# board.net
KiCad netlist of a schematic drawn in EAGLE
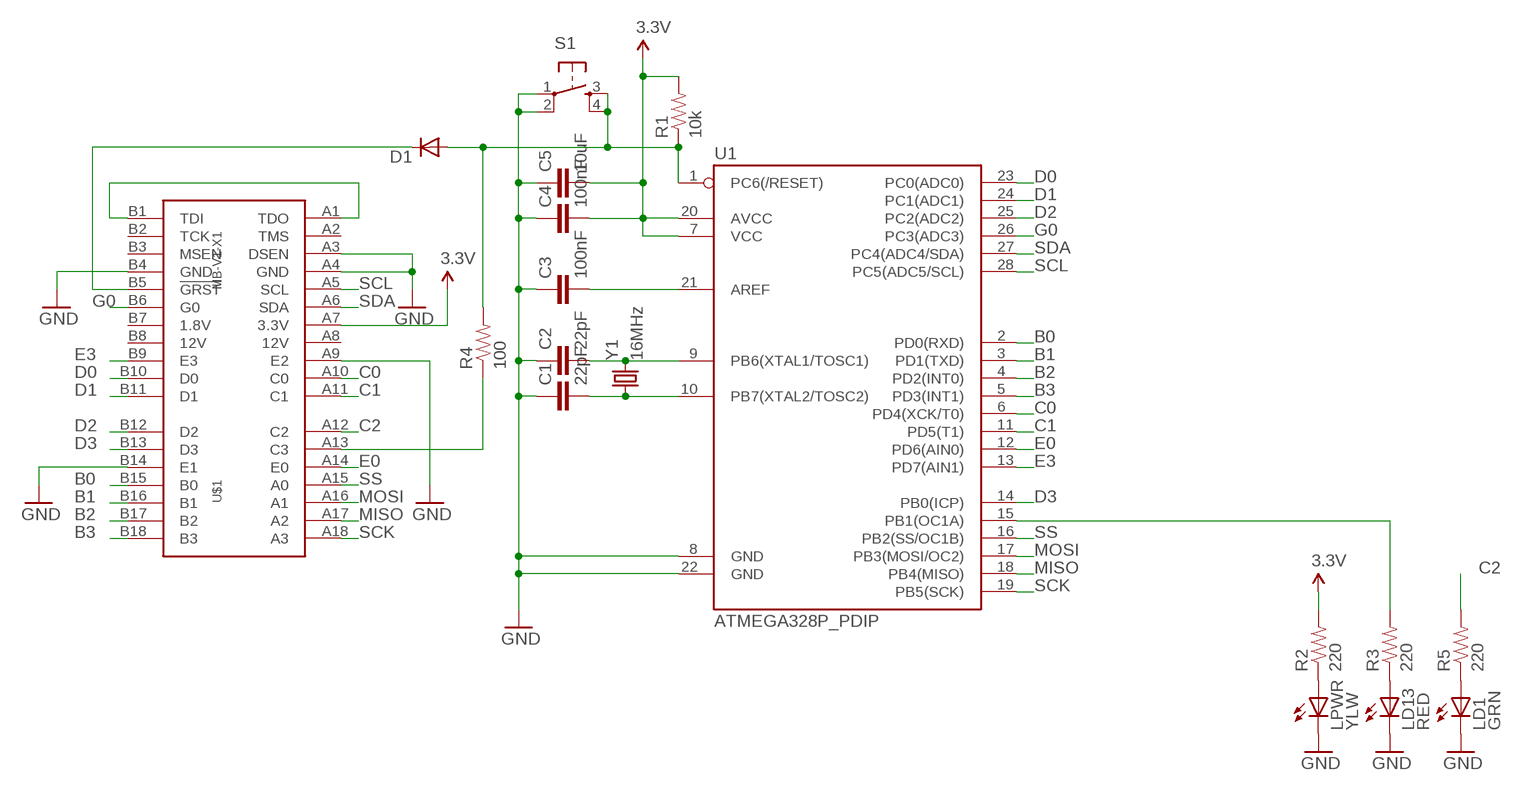
[diagram p0: schematic, sheet 1]

(export (version "E")
  (design (tool "Eeschema 10.0.6"))
  (components
    (comp (ref "C1")
      (value "22pF")
      (footprint "eagle-import:0402-CAP")
      (libsource (lib "eagle-import") (part "CAP0402-CAP"))
    )
    (comp (ref "C2")
      (value "22pF")
      (footprint "eagle-import:0402-CAP")
      (libsource (lib "eagle-import") (part "CAP0402-CAP"))
    )
    (comp (ref "C3")
      (value "100nF")
      (footprint "eagle-import:0402-CAP")
      (libsource (lib "eagle-import") (part "CAP0402-CAP"))
    )
    (comp (ref "C4")
      (value "100nF")
      (footprint "eagle-import:0402-CAP")
      (libsource (lib "eagle-import") (part "CAP0402-CAP"))
    )
    (comp (ref "C5")
      (value "10uF")
      (footprint "eagle-import:0805")
      (libsource (lib "eagle-import") (part "CAP0805"))
    )
    (comp (ref "D1")
      (value "DIODE1N4148")
      (footprint "eagle-import:DIODE-1N4148")
      (libsource (lib "eagle-import") (part "DIODE1N4148"))
    )
    (comp (ref "LD1")
      (value "GRN")
      (footprint "eagle-import:LED-0603")
      (libsource (lib "eagle-import") (part "LED-RED0603"))
    )
    (comp (ref "LD13")
      (value "RED")
      (footprint "eagle-import:LED-0603")
      (libsource (lib "eagle-import") (part "LED-RED0603"))
    )
    (comp (ref "LPWR")
      (value "YLW")
      (footprint "eagle-import:LED-0603")
      (libsource (lib "eagle-import") (part "LED-RED0603"))
    )
    (comp (ref "R1")
      (value "10k")
      (footprint "eagle-import:0603-RES")
      (libsource (lib "eagle-import") (part "kmod-passives_RESISTOR0603"))
    )
    (comp (ref "R2")
      (value "220")
      (footprint "eagle-import:0603-RES")
      (libsource (lib "eagle-import") (part "RESISTOR0603"))
    )
    (comp (ref "R3")
      (value "220")
      (footprint "eagle-import:0603-RES")
      (libsource (lib "eagle-import") (part "RESISTOR0603"))
    )
    (comp (ref "R4")
      (value "100")
      (footprint "eagle-import:0603-RES")
      (libsource (lib "eagle-import") (part "kmod-passives_RESISTOR0603"))
    )
    (comp (ref "R5")
      (value "220")
      (footprint "eagle-import:0603-RES")
      (libsource (lib "eagle-import") (part "RESISTOR0603"))
    )
    (comp (ref "S1")
      (value "TAC_SWITCHPTH")
      (footprint "eagle-import:TACTILE-PTH")
      (libsource (lib "eagle-import") (part "TAC_SWITCHPTH"))
    )
    (comp (ref "U$1")
      (value "MB-V1-X1")
      (footprint "eagle-import:PCIE-X1-EDGE")
      (libsource (lib "eagle-import") (part "MB-V1-X1"))
    )
    (comp (ref "U1")
      (value "ATMEGA328P_PDIP")
      (footprint "eagle-import:DIL28-3")
      (libsource (lib "eagle-import") (part "ATMEGA328P_PDIP"))
    )
    (comp (ref "Y1")
      (value "16MHz")
      (footprint "eagle-import:HC49US")
      (libsource (lib "eagle-import") (part "CRYSTALHC49US"))
    )
  )
  (nets
    (net (code "1") (name "/B0") (class "Default")
      (node (ref "U$1") (pin "B15") (pinfunction "B0_B15") (pintype "bidirectional"))
      (node (ref "U1") (pin "2") (pinfunction "PD0(RXD)_2") (pintype "bidirectional"))
    )
    (net (code "2") (name "/B1") (class "Default")
      (node (ref "U$1") (pin "B16") (pinfunction "B1_B16") (pintype "bidirectional"))
      (node (ref "U1") (pin "3") (pinfunction "PD1(TXD)_3") (pintype "bidirectional"))
    )
    (net (code "3") (name "/B2") (class "Default")
      (node (ref "U$1") (pin "B17") (pinfunction "B2_B17") (pintype "bidirectional"))
      (node (ref "U1") (pin "4") (pinfunction "PD2(INT0)_4") (pintype "bidirectional"))
    )
    (net (code "4") (name "/B3") (class "Default")
      (node (ref "U$1") (pin "B18") (pinfunction "B3_B18") (pintype "bidirectional"))
      (node (ref "U1") (pin "5") (pinfunction "PD3(INT1)_5") (pintype "bidirectional"))
    )
    (net (code "5") (name "/C0") (class "Default")
      (node (ref "U$1") (pin "A10") (pinfunction "C0_A10") (pintype "bidirectional"))
      (node (ref "U1") (pin "6") (pinfunction "PD4(XCK/T0)_6") (pintype "bidirectional"))
    )
    (net (code "6") (name "/C1") (class "Default")
      (node (ref "U$1") (pin "A11") (pinfunction "C1_A11") (pintype "bidirectional"))
      (node (ref "U1") (pin "11") (pinfunction "PD5(T1)_11") (pintype "bidirectional"))
    )
    (net (code "7") (name "/C2") (class "Default")
      (node (ref "R5") (pin "2") (pinfunction "2_2") (pintype "passive"))
      (node (ref "U$1") (pin "A12") (pinfunction "C2_A12") (pintype "bidirectional"))
    )
    (net (code "8") (name "/D0") (class "Default")
      (node (ref "U$1") (pin "B10") (pinfunction "D0_B10") (pintype "bidirectional"))
      (node (ref "U1") (pin "23") (pinfunction "PC0(ADC0)_23") (pintype "bidirectional"))
    )
    (net (code "9") (name "/D1") (class "Default")
      (node (ref "U$1") (pin "B11") (pinfunction "D1_B11") (pintype "bidirectional"))
      (node (ref "U1") (pin "24") (pinfunction "PC1(ADC1)_24") (pintype "bidirectional"))
    )
    (net (code "10") (name "/D2") (class "Default")
      (node (ref "U$1") (pin "B12") (pinfunction "D2_B12") (pintype "bidirectional"))
      (node (ref "U1") (pin "25") (pinfunction "PC2(ADC2)_25") (pintype "bidirectional"))
    )
    (net (code "11") (name "/D3") (class "Default")
      (node (ref "U$1") (pin "B13") (pinfunction "D3_B13") (pintype "bidirectional"))
      (node (ref "U1") (pin "14") (pinfunction "PB0(ICP)_14") (pintype "bidirectional"))
    )
    (net (code "12") (name "/E0") (class "Default")
      (node (ref "U$1") (pin "A14") (pinfunction "E0_A14") (pintype "bidirectional"))
      (node (ref "U1") (pin "12") (pinfunction "PD6(AIN0)_12") (pintype "bidirectional"))
    )
    (net (code "13") (name "/E3") (class "Default")
      (node (ref "U$1") (pin "B9") (pinfunction "E3_B9") (pintype "bidirectional"))
      (node (ref "U1") (pin "13") (pinfunction "PD7(AIN1)_13") (pintype "bidirectional"))
    )
    (net (code "14") (name "/G0") (class "Default")
      (node (ref "U$1") (pin "B6") (pinfunction "G0_B6") (pintype "bidirectional"))
      (node (ref "U1") (pin "26") (pinfunction "PC3(ADC3)_26") (pintype "bidirectional"))
    )
    (net (code "15") (name "/MISO") (class "Default")
      (node (ref "U$1") (pin "A17") (pinfunction "A2_A17") (pintype "bidirectional"))
      (node (ref "U1") (pin "18") (pinfunction "PB4(MISO)_18") (pintype "bidirectional"))
    )
    (net (code "16") (name "/MOSI") (class "Default")
      (node (ref "U$1") (pin "A16") (pinfunction "A1_A16") (pintype "bidirectional"))
      (node (ref "U1") (pin "17") (pinfunction "PB3(MOSI/OC2)_17") (pintype "bidirectional"))
    )
    (net (code "17") (name "/SCK") (class "Default")
      (node (ref "U$1") (pin "A18") (pinfunction "A3_A18") (pintype "bidirectional"))
      (node (ref "U1") (pin "19") (pinfunction "PB5(SCK)_19") (pintype "bidirectional"))
    )
    (net (code "18") (name "/SCL") (class "Default")
      (node (ref "U$1") (pin "A5") (pinfunction "SCL_A5") (pintype "bidirectional"))
      (node (ref "U1") (pin "28") (pinfunction "PC5(ADC5/SCL)_28") (pintype "bidirectional"))
    )
    (net (code "19") (name "/SDA") (class "Default")
      (node (ref "U$1") (pin "A6") (pinfunction "SDA_A6") (pintype "bidirectional"))
      (node (ref "U1") (pin "27") (pinfunction "PC4(ADC4/SDA)_27") (pintype "bidirectional"))
    )
    (net (code "20") (name "/SS") (class "Default")
      (node (ref "U$1") (pin "A15") (pinfunction "A0_A15") (pintype "bidirectional"))
      (node (ref "U1") (pin "16") (pinfunction "PB2(SS/OC1B)_16") (pintype "bidirectional"))
    )
    (net (code "21") (name "3.3V") (class "Default")
      (node (ref "C4") (pin "2") (pinfunction "2_2") (pintype "passive"))
      (node (ref "C5") (pin "2") (pinfunction "2_2") (pintype "passive"))
      (node (ref "R1") (pin "2") (pinfunction "2_2") (pintype "passive"))
      (node (ref "R2") (pin "2") (pinfunction "2_2") (pintype "passive"))
      (node (ref "U$1") (pin "A7") (pinfunction "3.3V_A7") (pintype "bidirectional"))
      (node (ref "U1") (pin "20") (pinfunction "AVCC_20") (pintype "bidirectional"))
      (node (ref "U1") (pin "7") (pinfunction "VCC_7") (pintype "bidirectional"))
    )
    (net (code "22") (name "GND") (class "Default")
      (node (ref "C1") (pin "1") (pinfunction "1_1") (pintype "passive"))
      (node (ref "C2") (pin "1") (pinfunction "1_1") (pintype "passive"))
      (node (ref "C3") (pin "1") (pinfunction "1_1") (pintype "passive"))
      (node (ref "C4") (pin "1") (pinfunction "1_1") (pintype "passive"))
      (node (ref "C5") (pin "1") (pinfunction "1_1") (pintype "passive"))
      (node (ref "LD1") (pin "C") (pinfunction "C_C") (pintype "passive"))
      (node (ref "LD13") (pin "C") (pinfunction "C_C") (pintype "passive"))
      (node (ref "LPWR") (pin "C") (pinfunction "C_C") (pintype "passive"))
      (node (ref "S1") (pin "1") (pinfunction "1_1") (pintype "passive"))
      (node (ref "S1") (pin "2") (pinfunction "2_2") (pintype "passive"))
      (node (ref "U$1") (pin "A3") (pinfunction "DSEN_A3") (pintype "bidirectional"))
      (node (ref "U$1") (pin "A4") (pinfunction "GND_A4") (pintype "bidirectional"))
      (node (ref "U$1") (pin "A9") (pinfunction "E2_A9") (pintype "bidirectional"))
      (node (ref "U$1") (pin "B14") (pinfunction "E1_B14") (pintype "bidirectional"))
      (node (ref "U$1") (pin "B4") (pinfunction "GND_B4") (pintype "bidirectional"))
      (node (ref "U1") (pin "22") (pinfunction "GND_22") (pintype "bidirectional"))
      (node (ref "U1") (pin "8") (pinfunction "GND_8") (pintype "bidirectional"))
    )
    (net (code "23") (name "Net-(LD1-PadA)") (class "Default")
      (node (ref "LD1") (pin "A") (pinfunction "A_A") (pintype "passive"))
      (node (ref "R5") (pin "1") (pinfunction "1_1") (pintype "passive"))
    )
    (net (code "24") (name "Net-(LD13-PadA)") (class "Default")
      (node (ref "LD13") (pin "A") (pinfunction "A_A") (pintype "passive"))
      (node (ref "R3") (pin "1") (pinfunction "1_1") (pintype "passive"))
    )
    (net (code "25") (name "Net-(LPWR-PadA)") (class "Default")
      (node (ref "LPWR") (pin "A") (pinfunction "A_A") (pintype "passive"))
      (node (ref "R2") (pin "1") (pinfunction "1_1") (pintype "passive"))
    )
    (net (code "26") (name "Net-(U$1-C3)") (class "Default")
      (node (ref "R4") (pin "1") (pinfunction "1_1") (pintype "passive"))
      (node (ref "U$1") (pin "A13") (pinfunction "C3_A13") (pintype "bidirectional"))
    )
    (net (code "27") (name "Net-(U$1-TDI)") (class "Default")
      (node (ref "U$1") (pin "A1") (pinfunction "TDO_A1") (pintype "bidirectional"))
      (node (ref "U$1") (pin "B1") (pinfunction "TDI_B1") (pintype "bidirectional"))
    )
    (net (code "28") (name "Net-(U$1-~{GRST})") (class "Default")
      (node (ref "D1") (pin "C") (pinfunction "C_C") (pintype "passive"))
      (node (ref "U$1") (pin "B5") (pinfunction "~{GRST}_B5") (pintype "bidirectional"))
    )
    (net (code "29") (name "Net-(U1-AREF)") (class "Default")
      (node (ref "C3") (pin "2") (pinfunction "2_2") (pintype "passive"))
      (node (ref "U1") (pin "21") (pinfunction "AREF_21") (pintype "bidirectional"))
    )
    (net (code "30") (name "Net-(U1-PB1(OC1A))") (class "Default")
      (node (ref "R3") (pin "2") (pinfunction "2_2") (pintype "passive"))
      (node (ref "U1") (pin "15") (pinfunction "PB1(OC1A)_15") (pintype "bidirectional"))
    )
    (net (code "31") (name "Net-(U1-PB6(XTAL1{slash}TOSC1))") (class "Default")
      (node (ref "C2") (pin "2") (pinfunction "2_2") (pintype "passive"))
      (node (ref "U1") (pin "9") (pinfunction "PB6(XTAL1/TOSC1)_9") (pintype "bidirectional"))
      (node (ref "Y1") (pin "2") (pinfunction "2_2") (pintype "passive"))
    )
    (net (code "32") (name "Net-(U1-PB7(XTAL2{slash}TOSC2))") (class "Default")
      (node (ref "C1") (pin "2") (pinfunction "2_2") (pintype "passive"))
      (node (ref "U1") (pin "10") (pinfunction "PB7(XTAL2/TOSC2)_10") (pintype "bidirectional"))
      (node (ref "Y1") (pin "1") (pinfunction "1_1") (pintype "passive"))
    )
    (net (code "33") (name "Net-(U1-PC6({slash}RESET))") (class "Default")
      (node (ref "D1") (pin "A") (pinfunction "A_A") (pintype "passive"))
      (node (ref "R1") (pin "1") (pinfunction "1_1") (pintype "passive"))
      (node (ref "R4") (pin "2") (pinfunction "2_2") (pintype "passive"))
      (node (ref "S1") (pin "3") (pinfunction "3_3") (pintype "passive"))
      (node (ref "S1") (pin "4") (pinfunction "4_4") (pintype "passive"))
      (node (ref "U1") (pin "1") (pinfunction "PC6(/RESET)_1") (pintype "bidirectional"))
    )
    (net (code "34") (name "unconnected-(U$1-1.8V-PadB7)") (class "Default")
      (node (ref "U$1") (pin "B7") (pinfunction "1.8V_B7") (pintype "bidirectional"))
    )
    (net (code "35") (name "unconnected-(U$1-12V-PadA8)") (class "Default")
      (node (ref "U$1") (pin "A8") (pinfunction "12V_A8") (pintype "bidirectional"))
    )
    (net (code "36") (name "unconnected-(U$1-12V-PadB8)") (class "Default")
      (node (ref "U$1") (pin "B8") (pinfunction "12V_B8") (pintype "bidirectional"))
    )
    (net (code "37") (name "unconnected-(U$1-MSEN-PadB3)") (class "Default")
      (node (ref "U$1") (pin "B3") (pinfunction "MSEN_B3") (pintype "bidirectional"))
    )
    (net (code "38") (name "unconnected-(U$1-TCK-PadB2)") (class "Default")
      (node (ref "U$1") (pin "B2") (pinfunction "TCK_B2") (pintype "bidirectional"))
    )
    (net (code "39") (name "unconnected-(U$1-TMS-PadA2)") (class "Default")
      (node (ref "U$1") (pin "A2") (pinfunction "TMS_A2") (pintype "bidirectional"))
    )
  )
)
